# 14-FPGA-01a.net
KiCad netlist of a schematic drawn in Altium Designer
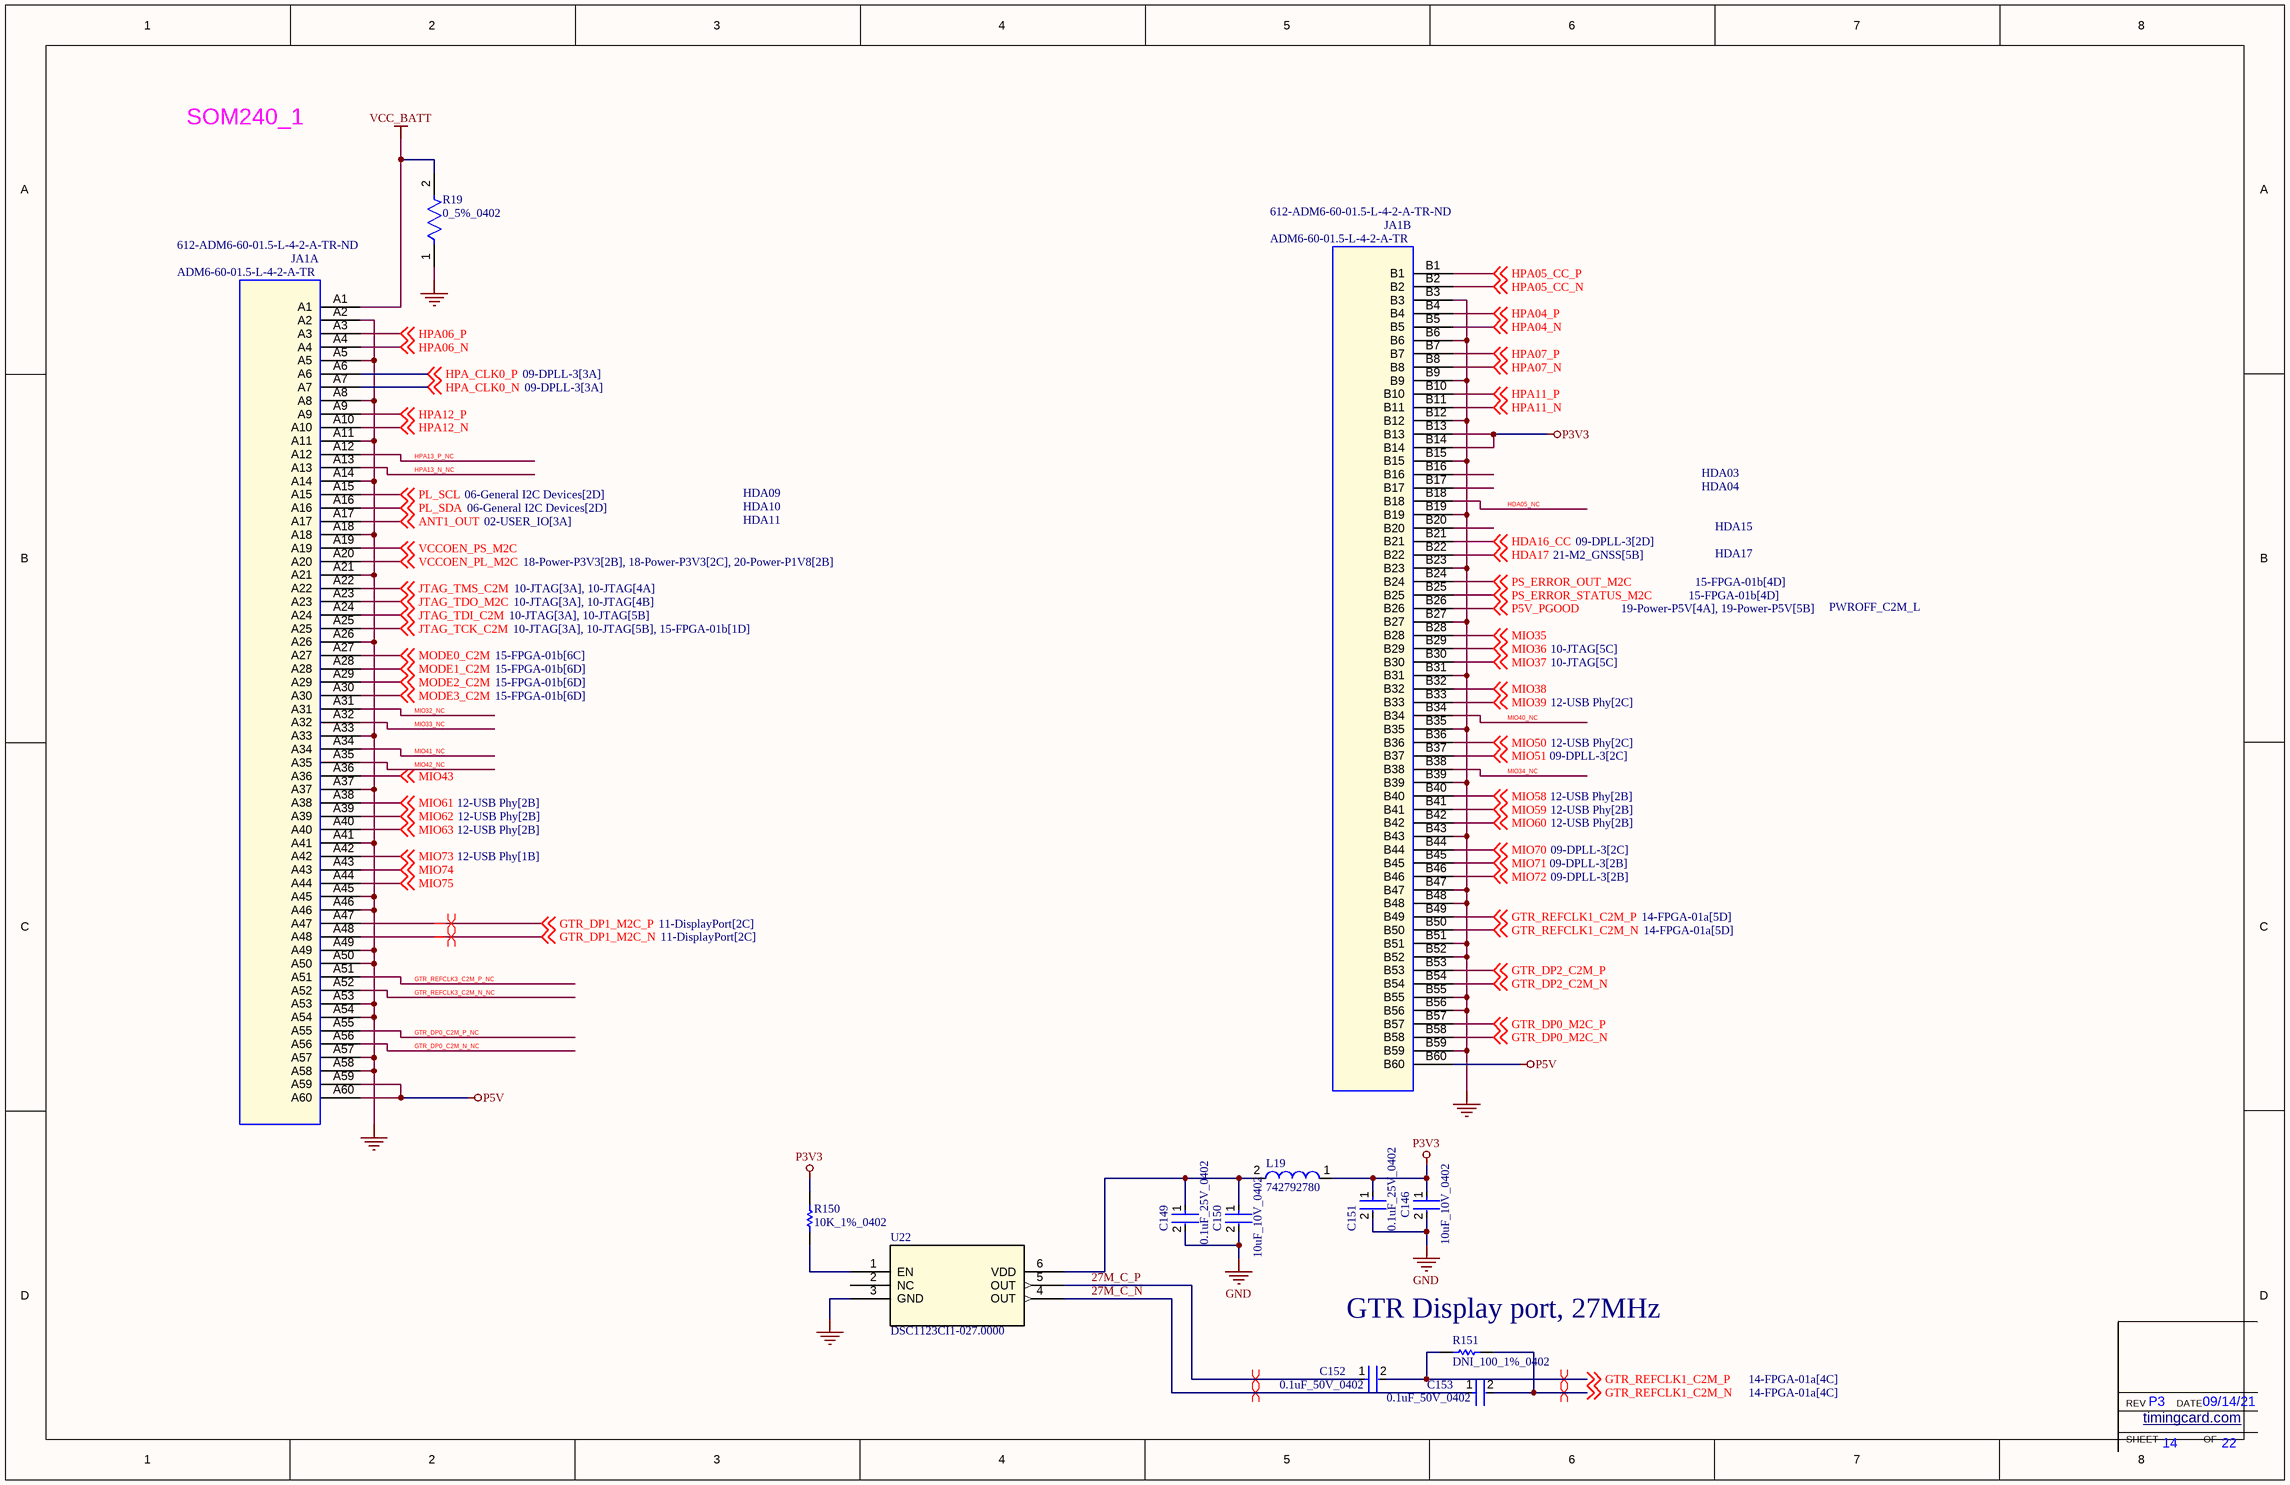
[diagram p0: 14-FPGA-01a.SchDoc]

(export (version "E")
  (design (tool "Eeschema 10.0.6"))
  (components
    (comp (ref "C146")
      (value "10uF_10V_0402")
      (footprint "FP-CL05A106MP5NUNC-MFG")
      (description "CAP CER 10UF 10V X5R 0402")
      (fields
        (field (name "OCTOPART") "https://octopart.com/cl05a106mp5nunc-samsung-22457395")
        (field (name "TOLERANCE") "20%")
      )
      (libsource (lib "Altium Content Vault") (part "b4654b650e69147ec39a6b967a45e02"))
    )
    (comp (ref "C149")
      (value "0.1uF_25V_0402")
      (footprint "FP-0402-L_1_0_1-W_0_5_0_1-IPC_C")
      (description "General Purpose Ceramic Capacitor, 0402, 100nF, 10%, X7R, 15%, 25V")
      (fields (field (name "VOLTAGE") "25V") (field (name "TOLERANCE") "10%"))
      (libsource (lib "Altium Content Vault") (part "b4654b650e69147ec39a6b967a45e02"))
    )
    (comp (ref "C150")
      (value "10uF_10V_0402")
      (footprint "FP-CL05A106MP5NUNC-MFG")
      (description "CAP CER 10UF 10V X5R 0402")
      (fields
        (field (name "OCTOPART") "https://octopart.com/cl05a106mp5nunc-samsung-22457395")
        (field (name "TOLERANCE") "20%")
      )
      (libsource (lib "Altium Content Vault") (part "b4654b650e69147ec39a6b967a45e02"))
    )
    (comp (ref "C151")
      (value "0.1uF_25V_0402")
      (footprint "FP-0402-L_1_0_1-W_0_5_0_1-IPC_C")
      (description "General Purpose Ceramic Capacitor, 0402, 100nF, 10%, X7R, 15%, 25V")
      (fields (field (name "VOLTAGE") "25V") (field (name "TOLERANCE") "10%"))
      (libsource (lib "Altium Content Vault") (part "b4654b650e69147ec39a6b967a45e02"))
    )
    (comp (ref "C152")
      (value "0.1uF_50V_0402")
      (footprint "FP-C1005-050-0_05-IPC_C")
      (description "Multilayer Ceramic Capacitors 100nF ±10% 50V X7R SMD 0402")
      (fields (field (name "VOLTAGE") "50V") (field (name "TOLERANCE") "10%"))
      (libsource (lib "Altium Content Vault") (part "b4654b650e69147ec39a6b967a45e02"))
    )
    (comp (ref "C153")
      (value "0.1uF_50V_0402")
      (footprint "FP-C1005-050-0_05-IPC_C")
      (description "Multilayer Ceramic Capacitors 100nF ±10% 50V X7R SMD 0402")
      (fields (field (name "VOLTAGE") "50V") (field (name "TOLERANCE") "10%"))
      (libsource (lib "Altium Content Vault") (part "b4654b650e69147ec39a6b967a45e02"))
    )
    (comp (ref "JA1")
      (value "ADM6-60-01.5-L-4-2-A-TR")
      (footprint "CON_SAMTEC_ADM6_60_4")
      (description "Conn Rcpt Male Vert 240 Pos 4x60 0.635mm P Black SMT")
      (fields
        (field (name "MANUFACTURER") "Samtec Inc.")
        (field (name "AGILE PART NUMBER") "CON-00383-01")
        (field (name "SUPPLIER PART NUMBER 1") "612-ADM6-60-01.5-L-4-2-A-TR-ND")
      )
      (libsource (lib "*") (part "SAMTEC-ADx6-60X4"))
    )
    (comp (ref "L19")
      (value "742792780")
      (footprint "SMD-0402")
      (description "SMD EMI Suppression Ferrite Bead WE-CBF, Z = 220 Ohm")
      (libsource (lib "Altium Content Vault") (part "PAS-IND-INDUCTOR-2"))
    )
    (comp (ref "R19")
      (value "0_5%_0402")
      (footprint "FP-AC0402-0_37-IPC_B")
      (description "RESISTOR 0402 JUMPER ZERO OHM")
      (fields (field (name "TOLERANCE") "1%"))
      (libsource (lib "Altium Content Vault") (part "1029c3af85768c4190bb7ad29bc67b5"))
    )
    (comp (ref "R150")
      (value "10K_1%_0402")
      (footprint "RESC1005X40X25LL05T05")
      (description "Chip Resistor, 10 KOhm, +/- 1%, 0.1 W, -55 to 155 degC, 0402 (1005 Metric), RoHS, Tape and Reel")
      (fields (field (name "TOLERANCE") "1%") (field (name "MANUFACTURER") "Panasonic"))
      (libsource (lib "Altium Content Vault") (part "RES-2"))
    )
    (comp (ref "R151")
      (value "DNI_100_1%_0402")
      (footprint "RESC1005X40X25ML05T10")
      (fields (field (name "PART NUMBER") "ERJ-U02F1000X") (field (name "MANUFACTURER") "Panasonic"))
      (libsource (lib "Altium Content Vault") (part "RES"))
    )
    (comp (ref "U22")
      (value "DSC1123CI1-027.0000")
      (footprint "VDFN6_3P2X2P5_MCH")
      (description "No Description Available")
      (libsource (lib "DSC1123CI1-027P0000") (part "DSC1123CI1-027.0000"))
    )
  )
  (nets
    (net (code "1") (name "/27M_C_N") (class "Default")
      (node (ref "C153") (pin "1") (pinfunction "1_1") (pintype "passive"))
      (node (ref "U22") (pin "4") (pinfunction "OUT_4") (pintype "output"))
    )
    (net (code "2") (name "/27M_C_P") (class "Default")
      (node (ref "C152") (pin "1") (pinfunction "1_1") (pintype "passive"))
      (node (ref "U22") (pin "5") (pinfunction "OUT_5") (pintype "output"))
    )
    (net (code "3") (name "/GTR_DP0_C2M_N_NC") (class "Default")
      (node (ref "JA1") (pin "A56") (pinfunction "A56_A56") (pintype "passive"))
    )
    (net (code "4") (name "/GTR_DP0_C2M_P_NC") (class "Default")
      (node (ref "JA1") (pin "A55") (pinfunction "A55_A55") (pintype "passive"))
    )
    (net (code "5") (name "/GTR_REFCLK3_C2M_N_NC") (class "Default")
      (node (ref "JA1") (pin "A52") (pinfunction "A52_A52") (pintype "passive"))
    )
    (net (code "6") (name "/GTR_REFCLK3_C2M_P_NC") (class "Default")
      (node (ref "JA1") (pin "A51") (pinfunction "A51_A51") (pintype "passive"))
    )
    (net (code "7") (name "/HDA05_NC") (class "Default")
      (node (ref "JA1") (pin "B18") (pinfunction "B18_B18") (pintype "passive"))
    )
    (net (code "8") (name "/HPA13_N_NC") (class "Default")
      (node (ref "JA1") (pin "A13") (pinfunction "A13_A13") (pintype "passive"))
    )
    (net (code "9") (name "/HPA13_P_NC") (class "Default")
      (node (ref "JA1") (pin "A12") (pinfunction "A12_A12") (pintype "passive"))
    )
    (net (code "10") (name "/MIO32_NC") (class "Default")
      (node (ref "JA1") (pin "A31") (pinfunction "A31_A31") (pintype "passive"))
    )
    (net (code "11") (name "/MIO33_NC") (class "Default")
      (node (ref "JA1") (pin "A32") (pinfunction "A32_A32") (pintype "passive"))
    )
    (net (code "12") (name "/MIO34_NC") (class "Default")
      (node (ref "JA1") (pin "B38") (pinfunction "B38_B38") (pintype "passive"))
    )
    (net (code "13") (name "/MIO40_NC") (class "Default")
      (node (ref "JA1") (pin "B34") (pinfunction "B34_B34") (pintype "passive"))
    )
    (net (code "14") (name "/MIO41_NC") (class "Default")
      (node (ref "JA1") (pin "A34") (pinfunction "A34_A34") (pintype "passive"))
    )
    (net (code "15") (name "/MIO42_NC") (class "Default")
      (node (ref "JA1") (pin "A35") (pinfunction "A35_A35") (pintype "passive"))
    )
    (net (code "16") (name "ANT1_OUT") (class "Default")
      (node (ref "JA1") (pin "A17") (pinfunction "A17_A17") (pintype "passive"))
    )
    (net (code "17") (name "GND") (class "Default")
      (node (ref "C146") (pin "2") (pinfunction "2_2") (pintype "passive"))
      (node (ref "C149") (pin "2") (pinfunction "2_2") (pintype "passive"))
      (node (ref "C150") (pin "2") (pinfunction "2_2") (pintype "passive"))
      (node (ref "C151") (pin "2") (pinfunction "2_2") (pintype "passive"))
      (node (ref "JA1") (pin "A11") (pinfunction "A11_A11") (pintype "passive"))
      (node (ref "JA1") (pin "A14") (pinfunction "A14_A14") (pintype "passive"))
      (node (ref "JA1") (pin "A18") (pinfunction "A18_A18") (pintype "passive"))
      (node (ref "JA1") (pin "A2") (pinfunction "A2_A2") (pintype "passive"))
      (node (ref "JA1") (pin "A21") (pinfunction "A21_A21") (pintype "passive"))
      (node (ref "JA1") (pin "A26") (pinfunction "A26_A26") (pintype "passive"))
      (node (ref "JA1") (pin "A33") (pinfunction "A33_A33") (pintype "passive"))
      (node (ref "JA1") (pin "A37") (pinfunction "A37_A37") (pintype "passive"))
      (node (ref "JA1") (pin "A41") (pinfunction "A41_A41") (pintype "passive"))
      (node (ref "JA1") (pin "A45") (pinfunction "A45_A45") (pintype "passive"))
      (node (ref "JA1") (pin "A46") (pinfunction "A46_A46") (pintype "passive"))
      (node (ref "JA1") (pin "A49") (pinfunction "A49_A49") (pintype "passive"))
      (node (ref "JA1") (pin "A5") (pinfunction "A5_A5") (pintype "passive"))
      (node (ref "JA1") (pin "A50") (pinfunction "A50_A50") (pintype "passive"))
      (node (ref "JA1") (pin "A53") (pinfunction "A53_A53") (pintype "passive"))
      (node (ref "JA1") (pin "A54") (pinfunction "A54_A54") (pintype "passive"))
      (node (ref "JA1") (pin "A57") (pinfunction "A57_A57") (pintype "passive"))
      (node (ref "JA1") (pin "A58") (pinfunction "A58_A58") (pintype "passive"))
      (node (ref "JA1") (pin "A8") (pinfunction "A8_A8") (pintype "passive"))
      (node (ref "JA1") (pin "B12") (pinfunction "B12_B12") (pintype "passive"))
      (node (ref "JA1") (pin "B15") (pinfunction "B15_B15") (pintype "passive"))
      (node (ref "JA1") (pin "B19") (pinfunction "B19_B19") (pintype "passive"))
      (node (ref "JA1") (pin "B23") (pinfunction "B23_B23") (pintype "passive"))
      (node (ref "JA1") (pin "B27") (pinfunction "B27_B27") (pintype "passive"))
      (node (ref "JA1") (pin "B3") (pinfunction "B3_B3") (pintype "passive"))
      (node (ref "JA1") (pin "B31") (pinfunction "B31_B31") (pintype "passive"))
      (node (ref "JA1") (pin "B35") (pinfunction "B35_B35") (pintype "passive"))
      (node (ref "JA1") (pin "B39") (pinfunction "B39_B39") (pintype "passive"))
      (node (ref "JA1") (pin "B43") (pinfunction "B43_B43") (pintype "passive"))
      (node (ref "JA1") (pin "B47") (pinfunction "B47_B47") (pintype "passive"))
      (node (ref "JA1") (pin "B48") (pinfunction "B48_B48") (pintype "passive"))
      (node (ref "JA1") (pin "B51") (pinfunction "B51_B51") (pintype "passive"))
      (node (ref "JA1") (pin "B52") (pinfunction "B52_B52") (pintype "passive"))
      (node (ref "JA1") (pin "B55") (pinfunction "B55_B55") (pintype "passive"))
      (node (ref "JA1") (pin "B56") (pinfunction "B56_B56") (pintype "passive"))
      (node (ref "JA1") (pin "B59") (pinfunction "B59_B59") (pintype "passive"))
      (node (ref "JA1") (pin "B6") (pinfunction "B6_B6") (pintype "passive"))
      (node (ref "JA1") (pin "B9") (pinfunction "B9_B9") (pintype "passive"))
      (node (ref "R19") (pin "1") (pinfunction "1_1") (pintype "passive"))
      (node (ref "U22") (pin "3") (pinfunction "GND_3") (pintype "power_in"))
    )
    (net (code "18") (name "GTR_DP0_M2C_N") (class "Default")
      (node (ref "JA1") (pin "B58") (pinfunction "B58_B58") (pintype "passive"))
    )
    (net (code "19") (name "GTR_DP0_M2C_P") (class "Default")
      (node (ref "JA1") (pin "B57") (pinfunction "B57_B57") (pintype "passive"))
    )
    (net (code "20") (name "GTR_DP1_M2C_N") (class "Default")
      (node (ref "JA1") (pin "A48") (pinfunction "A48_A48") (pintype "passive"))
    )
    (net (code "21") (name "GTR_DP1_M2C_P") (class "Default")
      (node (ref "JA1") (pin "A47") (pinfunction "A47_A47") (pintype "passive"))
    )
    (net (code "22") (name "GTR_DP2_C2M_N") (class "Default")
      (node (ref "JA1") (pin "B54") (pinfunction "B54_B54") (pintype "passive"))
    )
    (net (code "23") (name "GTR_DP2_C2M_P") (class "Default")
      (node (ref "JA1") (pin "B53") (pinfunction "B53_B53") (pintype "passive"))
    )
    (net (code "24") (name "GTR_REFCLK1_C2M_N") (class "Default")
      (node (ref "C153") (pin "2") (pinfunction "2_2") (pintype "passive"))
      (node (ref "JA1") (pin "B50") (pinfunction "B50_B50") (pintype "passive"))
      (node (ref "R151") (pin "2") (pinfunction "2_2") (pintype "passive"))
    )
    (net (code "25") (name "GTR_REFCLK1_C2M_P") (class "Default")
      (node (ref "C152") (pin "2") (pinfunction "2_2") (pintype "passive"))
      (node (ref "JA1") (pin "B49") (pinfunction "B49_B49") (pintype "passive"))
      (node (ref "R151") (pin "1") (pinfunction "1_1") (pintype "passive"))
    )
    (net (code "26") (name "HDA16_CC") (class "Default")
      (node (ref "JA1") (pin "B21") (pinfunction "B21_B21") (pintype "passive"))
    )
    (net (code "27") (name "HDA17") (class "Default")
      (node (ref "JA1") (pin "B22") (pinfunction "B22_B22") (pintype "passive"))
    )
    (net (code "28") (name "HPA04_N") (class "Default")
      (node (ref "JA1") (pin "B5") (pinfunction "B5_B5") (pintype "passive"))
    )
    (net (code "29") (name "HPA04_P") (class "Default")
      (node (ref "JA1") (pin "B4") (pinfunction "B4_B4") (pintype "passive"))
    )
    (net (code "30") (name "HPA05_CC_N") (class "Default")
      (node (ref "JA1") (pin "B2") (pinfunction "B2_B2") (pintype "passive"))
    )
    (net (code "31") (name "HPA05_CC_P") (class "Default")
      (node (ref "JA1") (pin "B1") (pinfunction "B1_B1") (pintype "passive"))
    )
    (net (code "32") (name "HPA06_N") (class "Default")
      (node (ref "JA1") (pin "A4") (pinfunction "A4_A4") (pintype "passive"))
    )
    (net (code "33") (name "HPA06_P") (class "Default")
      (node (ref "JA1") (pin "A3") (pinfunction "A3_A3") (pintype "passive"))
    )
    (net (code "34") (name "HPA07_N") (class "Default")
      (node (ref "JA1") (pin "B8") (pinfunction "B8_B8") (pintype "passive"))
    )
    (net (code "35") (name "HPA07_P") (class "Default")
      (node (ref "JA1") (pin "B7") (pinfunction "B7_B7") (pintype "passive"))
    )
    (net (code "36") (name "HPA11_N") (class "Default")
      (node (ref "JA1") (pin "B11") (pinfunction "B11_B11") (pintype "passive"))
    )
    (net (code "37") (name "HPA11_P") (class "Default")
      (node (ref "JA1") (pin "B10") (pinfunction "B10_B10") (pintype "passive"))
    )
    (net (code "38") (name "HPA12_N") (class "Default")
      (node (ref "JA1") (pin "A10") (pinfunction "A10_A10") (pintype "passive"))
    )
    (net (code "39") (name "HPA12_P") (class "Default")
      (node (ref "JA1") (pin "A9") (pinfunction "A9_A9") (pintype "passive"))
    )
    (net (code "40") (name "HPA_CLK0_N") (class "Default")
      (node (ref "JA1") (pin "A7") (pinfunction "A7_A7") (pintype "passive"))
    )
    (net (code "41") (name "HPA_CLK0_P") (class "Default")
      (node (ref "JA1") (pin "A6") (pinfunction "A6_A6") (pintype "passive"))
    )
    (net (code "42") (name "JTAG_TCK_C2M") (class "Default")
      (node (ref "JA1") (pin "A25") (pinfunction "A25_A25") (pintype "passive"))
    )
    (net (code "43") (name "JTAG_TDI_C2M") (class "Default")
      (node (ref "JA1") (pin "A24") (pinfunction "A24_A24") (pintype "passive"))
    )
    (net (code "44") (name "JTAG_TDO_M2C") (class "Default")
      (node (ref "JA1") (pin "A23") (pinfunction "A23_A23") (pintype "passive"))
    )
    (net (code "45") (name "JTAG_TMS_C2M") (class "Default")
      (node (ref "JA1") (pin "A22") (pinfunction "A22_A22") (pintype "passive"))
    )
    (net (code "46") (name "MIO35") (class "Default")
      (node (ref "JA1") (pin "B28") (pinfunction "B28_B28") (pintype "passive"))
    )
    (net (code "47") (name "MIO36") (class "Default")
      (node (ref "JA1") (pin "B29") (pinfunction "B29_B29") (pintype "passive"))
    )
    (net (code "48") (name "MIO37") (class "Default")
      (node (ref "JA1") (pin "B30") (pinfunction "B30_B30") (pintype "passive"))
    )
    (net (code "49") (name "MIO38") (class "Default")
      (node (ref "JA1") (pin "B32") (pinfunction "B32_B32") (pintype "passive"))
    )
    (net (code "50") (name "MIO39") (class "Default")
      (node (ref "JA1") (pin "B33") (pinfunction "B33_B33") (pintype "passive"))
    )
    (net (code "51") (name "MIO43") (class "Default")
      (node (ref "JA1") (pin "A36") (pinfunction "A36_A36") (pintype "passive"))
    )
    (net (code "52") (name "MIO50") (class "Default")
      (node (ref "JA1") (pin "B36") (pinfunction "B36_B36") (pintype "passive"))
    )
    (net (code "53") (name "MIO51") (class "Default")
      (node (ref "JA1") (pin "B37") (pinfunction "B37_B37") (pintype "passive"))
    )
    (net (code "54") (name "MIO58") (class "Default")
      (node (ref "JA1") (pin "B40") (pinfunction "B40_B40") (pintype "passive"))
    )
    (net (code "55") (name "MIO59") (class "Default")
      (node (ref "JA1") (pin "B41") (pinfunction "B41_B41") (pintype "passive"))
    )
    (net (code "56") (name "MIO60") (class "Default")
      (node (ref "JA1") (pin "B42") (pinfunction "B42_B42") (pintype "passive"))
    )
    (net (code "57") (name "MIO61") (class "Default")
      (node (ref "JA1") (pin "A38") (pinfunction "A38_A38") (pintype "passive"))
    )
    (net (code "58") (name "MIO62") (class "Default")
      (node (ref "JA1") (pin "A39") (pinfunction "A39_A39") (pintype "passive"))
    )
    (net (code "59") (name "MIO63") (class "Default")
      (node (ref "JA1") (pin "A40") (pinfunction "A40_A40") (pintype "passive"))
    )
    (net (code "60") (name "MIO70") (class "Default")
      (node (ref "JA1") (pin "B44") (pinfunction "B44_B44") (pintype "passive"))
    )
    (net (code "61") (name "MIO71") (class "Default")
      (node (ref "JA1") (pin "B45") (pinfunction "B45_B45") (pintype "passive"))
    )
    (net (code "62") (name "MIO72") (class "Default")
      (node (ref "JA1") (pin "B46") (pinfunction "B46_B46") (pintype "passive"))
    )
    (net (code "63") (name "MIO73") (class "Default")
      (node (ref "JA1") (pin "A42") (pinfunction "A42_A42") (pintype "passive"))
    )
    (net (code "64") (name "MIO74") (class "Default")
      (node (ref "JA1") (pin "A43") (pinfunction "A43_A43") (pintype "passive"))
    )
    (net (code "65") (name "MIO75") (class "Default")
      (node (ref "JA1") (pin "A44") (pinfunction "A44_A44") (pintype "passive"))
    )
    (net (code "66") (name "MODE0_C2M") (class "Default")
      (node (ref "JA1") (pin "A27") (pinfunction "A27_A27") (pintype "passive"))
    )
    (net (code "67") (name "MODE1_C2M") (class "Default")
      (node (ref "JA1") (pin "A28") (pinfunction "A28_A28") (pintype "passive"))
    )
    (net (code "68") (name "MODE2_C2M") (class "Default")
      (node (ref "JA1") (pin "A29") (pinfunction "A29_A29") (pintype "passive"))
    )
    (net (code "69") (name "MODE3_C2M") (class "Default")
      (node (ref "JA1") (pin "A30") (pinfunction "A30_A30") (pintype "passive"))
    )
    (net (code "70") (name "Net-(U22-EN)") (class "Default")
      (node (ref "R150") (pin "1") (pinfunction "1_1") (pintype "passive"))
      (node (ref "U22") (pin "1") (pinfunction "EN_1") (pintype "passive"))
    )
    (net (code "71") (name "Net-(U22-VDD)") (class "Default")
      (node (ref "C149") (pin "1") (pinfunction "1_1") (pintype "passive"))
      (node (ref "C150") (pin "1") (pinfunction "1_1") (pintype "passive"))
      (node (ref "L19") (pin "2") (pinfunction "2_2") (pintype "passive"))
      (node (ref "U22") (pin "6") (pinfunction "VDD_6") (pintype "power_in"))
    )
    (net (code "72") (name "P3V3") (class "Default")
      (node (ref "C146") (pin "1") (pinfunction "1_1") (pintype "passive"))
      (node (ref "C151") (pin "1") (pinfunction "1_1") (pintype "passive"))
      (node (ref "JA1") (pin "B13") (pinfunction "B13_B13") (pintype "passive"))
      (node (ref "JA1") (pin "B14") (pinfunction "B14_B14") (pintype "passive"))
      (node (ref "L19") (pin "1") (pinfunction "1_1") (pintype "passive"))
      (node (ref "R150") (pin "2") (pinfunction "2_2") (pintype "passive"))
    )
    (net (code "73") (name "P5V") (class "Default")
      (node (ref "JA1") (pin "A59") (pinfunction "A59_A59") (pintype "passive"))
      (node (ref "JA1") (pin "A60") (pinfunction "A60_A60") (pintype "passive"))
      (node (ref "JA1") (pin "B60") (pinfunction "B60_B60") (pintype "passive"))
    )
    (net (code "74") (name "P5V_PGOOD") (class "Default")
      (node (ref "JA1") (pin "B26") (pinfunction "B26_B26") (pintype "passive"))
    )
    (net (code "75") (name "PL_SCL") (class "Default")
      (node (ref "JA1") (pin "A15") (pinfunction "A15_A15") (pintype "passive"))
    )
    (net (code "76") (name "PL_SDA") (class "Default")
      (node (ref "JA1") (pin "A16") (pinfunction "A16_A16") (pintype "passive"))
    )
    (net (code "77") (name "PS_ERROR_OUT_M2C") (class "Default")
      (node (ref "JA1") (pin "B24") (pinfunction "B24_B24") (pintype "passive"))
    )
    (net (code "78") (name "PS_ERROR_STATUS_M2C") (class "Default")
      (node (ref "JA1") (pin "B25") (pinfunction "B25_B25") (pintype "passive"))
    )
    (net (code "79") (name "VCCOEN_PL_M2C") (class "Default")
      (node (ref "JA1") (pin "A20") (pinfunction "A20_A20") (pintype "passive"))
    )
    (net (code "80") (name "VCCOEN_PS_M2C") (class "Default")
      (node (ref "JA1") (pin "A19") (pinfunction "A19_A19") (pintype "passive"))
    )
    (net (code "81") (name "VCC_BATT") (class "Default")
      (node (ref "JA1") (pin "A1") (pinfunction "A1_A1") (pintype "passive"))
      (node (ref "R19") (pin "2") (pinfunction "2_2") (pintype "passive"))
    )
    (net (code "82") (name "unconnected-(JA1-PadB16)") (class "Default")
      (node (ref "JA1") (pin "B16") (pinfunction "B16_B16") (pintype "passive"))
    )
    (net (code "83") (name "unconnected-(JA1-PadB17)") (class "Default")
      (node (ref "JA1") (pin "B17") (pinfunction "B17_B17") (pintype "passive"))
    )
    (net (code "84") (name "unconnected-(JA1-PadB20)") (class "Default")
      (node (ref "JA1") (pin "B20") (pinfunction "B20_B20") (pintype "passive"))
    )
    (net (code "85") (name "unconnected-(U22-NC-Pad2)") (class "Default")
      (node (ref "U22") (pin "2") (pinfunction "NC_2") (pintype "passive"))
    )
  )
)
